# Pentabyte_PCB_schematic.net
KiCad netlist of a schematic drawn in EAGLE
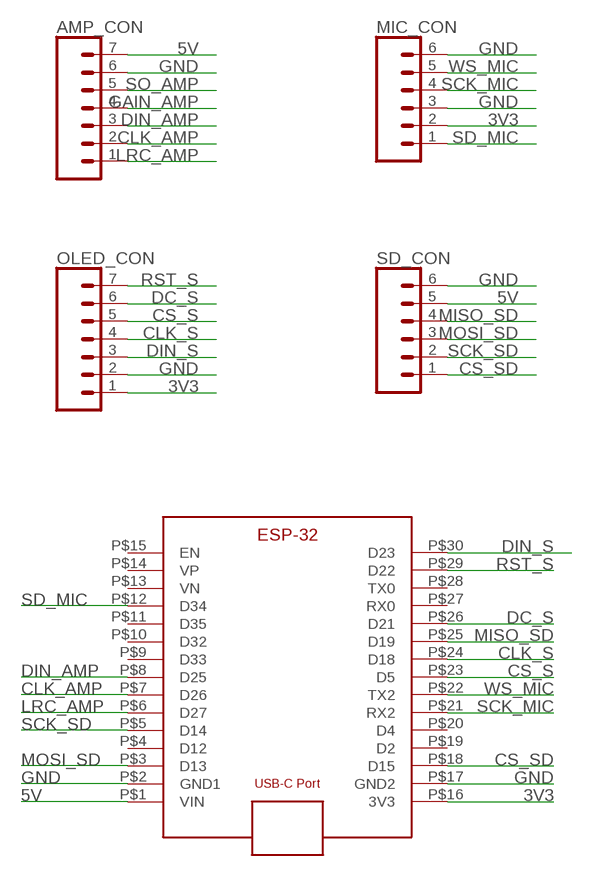
[diagram p0: schematic, sheet 1]

(export (version "E")
  (design (tool "Eeschema 10.0.6"))
  (components
    (comp (ref "AMP_CON")
      (value "CONN_07")
      (footprint "eagle-import:1X07")
      (libsource (lib "eagle-import") (part "CONN_07"))
    )
    (comp (ref "MIC_CON")
      (value "CONN_06SILK_FEMALE_PTH")
      (footprint "eagle-import:1X06")
      (libsource (lib "eagle-import") (part "CONN_06SILK_FEMALE_PTH"))
    )
    (comp (ref "OLED_CON")
      (value "CONN_07")
      (footprint "eagle-import:1X07")
      (libsource (lib "eagle-import") (part "CONN_07"))
    )
    (comp (ref "SD_CON")
      (value "CONN_06SILK_FEMALE_PTH")
      (footprint "eagle-import:1X06")
      (libsource (lib "eagle-import") (part "CONN_06SILK_FEMALE_PTH"))
    )
    (comp (ref "U$1")
      (value "ESP-WROOM-32_DEVKITESP-WROOM-32")
      (footprint "eagle-import:ESP-WROOM-32")
      (libsource (lib "eagle-import") (part "ESP-WROOM-32_DEVKITESP-WROOM-32"))
    )
  )
  (nets
    (net (code "1") (name "/3V3") (class "Default")
      (node (ref "MIC_CON") (pin "2") (pinfunction "2_2") (pintype "passive"))
      (node (ref "OLED_CON") (pin "1") (pinfunction "1_1") (pintype "passive"))
      (node (ref "U$1") (pin "P$16") (pinfunction "3V3_P$16") (pintype "bidirectional"))
    )
    (net (code "2") (name "/5V") (class "Default")
      (node (ref "AMP_CON") (pin "7") (pinfunction "7_7") (pintype "passive"))
      (node (ref "SD_CON") (pin "5") (pinfunction "5_5") (pintype "passive"))
      (node (ref "U$1") (pin "P$1") (pinfunction "VIN_P$1") (pintype "bidirectional"))
    )
    (net (code "3") (name "/CLK_AMP") (class "Default")
      (node (ref "AMP_CON") (pin "2") (pinfunction "2_2") (pintype "passive"))
      (node (ref "U$1") (pin "P$7") (pinfunction "D26_P$7") (pintype "bidirectional"))
    )
    (net (code "4") (name "/CLK_S") (class "Default")
      (node (ref "OLED_CON") (pin "4") (pinfunction "4_4") (pintype "passive"))
      (node (ref "U$1") (pin "P$24") (pinfunction "D18_P$24") (pintype "bidirectional"))
    )
    (net (code "5") (name "/CS_S") (class "Default")
      (node (ref "OLED_CON") (pin "5") (pinfunction "5_5") (pintype "passive"))
      (node (ref "U$1") (pin "P$23") (pinfunction "D5_P$23") (pintype "bidirectional"))
    )
    (net (code "6") (name "/CS_SD") (class "Default")
      (node (ref "SD_CON") (pin "1") (pinfunction "1_1") (pintype "passive"))
      (node (ref "U$1") (pin "P$18") (pinfunction "D15_P$18") (pintype "bidirectional"))
    )
    (net (code "7") (name "/DC_S") (class "Default")
      (node (ref "OLED_CON") (pin "6") (pinfunction "6_6") (pintype "passive"))
      (node (ref "U$1") (pin "P$26") (pinfunction "D21_P$26") (pintype "bidirectional"))
    )
    (net (code "8") (name "/DIN_AMP") (class "Default")
      (node (ref "AMP_CON") (pin "3") (pinfunction "3_3") (pintype "passive"))
      (node (ref "U$1") (pin "P$8") (pinfunction "D25_P$8") (pintype "bidirectional"))
    )
    (net (code "9") (name "/DIN_S") (class "Default")
      (node (ref "OLED_CON") (pin "3") (pinfunction "3_3") (pintype "passive"))
      (node (ref "U$1") (pin "P$30") (pinfunction "D23_P$30") (pintype "bidirectional"))
    )
    (net (code "10") (name "/GAIN_AMP") (class "Default")
      (node (ref "AMP_CON") (pin "4") (pinfunction "4_4") (pintype "passive"))
    )
    (net (code "11") (name "/GND") (class "Default")
      (node (ref "AMP_CON") (pin "6") (pinfunction "6_6") (pintype "passive"))
      (node (ref "MIC_CON") (pin "3") (pinfunction "3_3") (pintype "passive"))
      (node (ref "MIC_CON") (pin "6") (pinfunction "6_6") (pintype "passive"))
      (node (ref "OLED_CON") (pin "2") (pinfunction "2_2") (pintype "passive"))
      (node (ref "SD_CON") (pin "6") (pinfunction "6_6") (pintype "passive"))
      (node (ref "U$1") (pin "P$17") (pinfunction "GND2_P$17") (pintype "bidirectional"))
      (node (ref "U$1") (pin "P$2") (pinfunction "GND1_P$2") (pintype "bidirectional"))
    )
    (net (code "12") (name "/LRC_AMP") (class "Default")
      (node (ref "AMP_CON") (pin "1") (pinfunction "1_1") (pintype "passive"))
      (node (ref "U$1") (pin "P$6") (pinfunction "D27_P$6") (pintype "bidirectional"))
    )
    (net (code "13") (name "/MISO_SD") (class "Default")
      (node (ref "SD_CON") (pin "4") (pinfunction "4_4") (pintype "passive"))
      (node (ref "U$1") (pin "P$25") (pinfunction "D19_P$25") (pintype "bidirectional"))
    )
    (net (code "14") (name "/MOSI_SD") (class "Default")
      (node (ref "SD_CON") (pin "3") (pinfunction "3_3") (pintype "passive"))
      (node (ref "U$1") (pin "P$3") (pinfunction "D13_P$3") (pintype "bidirectional"))
    )
    (net (code "15") (name "/RST_S") (class "Default")
      (node (ref "OLED_CON") (pin "7") (pinfunction "7_7") (pintype "passive"))
      (node (ref "U$1") (pin "P$29") (pinfunction "D22_P$29") (pintype "bidirectional"))
    )
    (net (code "16") (name "/SCK_MIC") (class "Default")
      (node (ref "MIC_CON") (pin "4") (pinfunction "4_4") (pintype "passive"))
      (node (ref "U$1") (pin "P$21") (pinfunction "RX2_P$21") (pintype "bidirectional"))
    )
    (net (code "17") (name "/SCK_SD") (class "Default")
      (node (ref "SD_CON") (pin "2") (pinfunction "2_2") (pintype "passive"))
      (node (ref "U$1") (pin "P$5") (pinfunction "D14_P$5") (pintype "bidirectional"))
    )
    (net (code "18") (name "/SD_MIC") (class "Default")
      (node (ref "MIC_CON") (pin "1") (pinfunction "1_1") (pintype "passive"))
      (node (ref "U$1") (pin "P$12") (pinfunction "D34_P$12") (pintype "bidirectional"))
    )
    (net (code "19") (name "/SO_AMP") (class "Default")
      (node (ref "AMP_CON") (pin "5") (pinfunction "5_5") (pintype "passive"))
    )
    (net (code "20") (name "/WS_MIC") (class "Default")
      (node (ref "MIC_CON") (pin "5") (pinfunction "5_5") (pintype "passive"))
      (node (ref "U$1") (pin "P$22") (pinfunction "TX2_P$22") (pintype "bidirectional"))
    )
    (net (code "21") (name "unconnected-(U$1-D2-PadP$19)") (class "Default")
      (node (ref "U$1") (pin "P$19") (pinfunction "D2_P$19") (pintype "bidirectional"))
    )
    (net (code "22") (name "unconnected-(U$1-D4-PadP$20)") (class "Default")
      (node (ref "U$1") (pin "P$20") (pinfunction "D4_P$20") (pintype "bidirectional"))
    )
    (net (code "23") (name "unconnected-(U$1-D12-PadP$4)") (class "Default")
      (node (ref "U$1") (pin "P$4") (pinfunction "D12_P$4") (pintype "bidirectional"))
    )
    (net (code "24") (name "unconnected-(U$1-D32-PadP$10)") (class "Default")
      (node (ref "U$1") (pin "P$10") (pinfunction "D32_P$10") (pintype "bidirectional"))
    )
    (net (code "25") (name "unconnected-(U$1-D33-PadP$9)") (class "Default")
      (node (ref "U$1") (pin "P$9") (pinfunction "D33_P$9") (pintype "bidirectional"))
    )
    (net (code "26") (name "unconnected-(U$1-D35-PadP$11)") (class "Default")
      (node (ref "U$1") (pin "P$11") (pinfunction "D35_P$11") (pintype "bidirectional"))
    )
    (net (code "27") (name "unconnected-(U$1-EN-PadP$15)") (class "Default")
      (node (ref "U$1") (pin "P$15") (pinfunction "EN_P$15") (pintype "bidirectional"))
    )
    (net (code "28") (name "unconnected-(U$1-RX0-PadP$27)") (class "Default")
      (node (ref "U$1") (pin "P$27") (pinfunction "RX0_P$27") (pintype "bidirectional"))
    )
    (net (code "29") (name "unconnected-(U$1-TX0-PadP$28)") (class "Default")
      (node (ref "U$1") (pin "P$28") (pinfunction "TX0_P$28") (pintype "bidirectional"))
    )
    (net (code "30") (name "unconnected-(U$1-VN-PadP$13)") (class "Default")
      (node (ref "U$1") (pin "P$13") (pinfunction "VN_P$13") (pintype "bidirectional"))
    )
    (net (code "31") (name "unconnected-(U$1-VP-PadP$14)") (class "Default")
      (node (ref "U$1") (pin "P$14") (pinfunction "VP_P$14") (pintype "bidirectional"))
    )
  )
)
